# Sheet2.net
KiCad netlist of a schematic drawn in Altium Designer
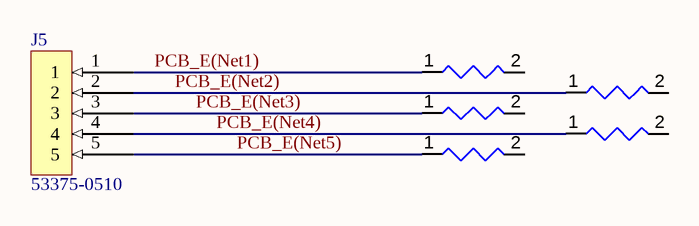
[diagram p0: Sheet2.SchDoc]

(export (version "E")
  (design (tool "Eeschema 10.0.6"))
  (components
    (comp (ref "J5")
      (value "53375-0510")
      (footprint "53375-0510-Footprint-1")
      (fields (field (name "MANUFACTURER") "Molex"))
      (libsource (lib "SCH") (part "CMP-002-00076-3"))
    )
    (comp (ref "R1")
      (value "Resistor 10k +/-1% 1206 250 mW")
      (footprint "RESC3216X60X45ML15T20")
      (description "Chip Resistor, 10 KOhm, +/- 1%, 0.25 W, -55 to 155 degC, 1206 (3216 Metric)")
      (fields (field (name "TOLERANCE") "1%") (field (name "POWER") "250mW"))
      (libsource (lib "SCH") (part "RES-2"))
    )
    (comp (ref "R2")
      (value "Resistor 10k +/-1% 1206 250 mW")
      (footprint "RESC3216X60X45ML15T20")
      (description "Chip Resistor, 10 KOhm, +/- 1%, 0.25 W, -55 to 155 degC, 1206 (3216 Metric)")
      (fields (field (name "TOLERANCE") "1%") (field (name "POWER") "250mW"))
      (libsource (lib "SCH") (part "RES-2"))
    )
    (comp (ref "R3")
      (value "Resistor 10k +/-1% 1206 250 mW")
      (footprint "RESC3216X60X45ML15T20")
      (description "Chip Resistor, 10 KOhm, +/- 1%, 0.25 W, -55 to 155 degC, 1206 (3216 Metric)")
      (fields (field (name "TOLERANCE") "1%") (field (name "POWER") "250mW"))
      (libsource (lib "SCH") (part "RES-2"))
    )
    (comp (ref "R4")
      (value "Resistor 10k +/-1% 1206 250 mW")
      (footprint "RESC3216X60X45ML15T20")
      (description "Chip Resistor, 10 KOhm, +/- 1%, 0.25 W, -55 to 155 degC, 1206 (3216 Metric)")
      (fields (field (name "TOLERANCE") "1%") (field (name "POWER") "250mW"))
      (libsource (lib "SCH") (part "RES-2"))
    )
    (comp (ref "R5")
      (value "Resistor 10k +/-1% 1206 250 mW")
      (footprint "RESC3216X60X45ML15T20")
      (description "Chip Resistor, 10 KOhm, +/- 1%, 0.25 W, -55 to 155 degC, 1206 (3216 Metric)")
      (fields (field (name "TOLERANCE") "1%") (field (name "POWER") "250mW"))
      (libsource (lib "SCH") (part "RES-2"))
    )
  )
  (nets
    (net (code "1") (name "/PCB_E(Net1)") (class "Default")
      (node (ref "J5") (pin "1") (pinfunction "1_1") (pintype "input"))
      (node (ref "R1") (pin "1") (pinfunction "1_1") (pintype "passive"))
    )
    (net (code "2") (name "/PCB_E(Net2)") (class "Default")
      (node (ref "J5") (pin "2") (pinfunction "2_2") (pintype "input"))
      (node (ref "R2") (pin "1") (pinfunction "1_1") (pintype "passive"))
    )
    (net (code "3") (name "/PCB_E(Net3)") (class "Default")
      (node (ref "J5") (pin "3") (pinfunction "3_3") (pintype "input"))
      (node (ref "R3") (pin "1") (pinfunction "1_1") (pintype "passive"))
    )
    (net (code "4") (name "/PCB_E(Net4)") (class "Default")
      (node (ref "J5") (pin "4") (pinfunction "4_4") (pintype "input"))
      (node (ref "R4") (pin "1") (pinfunction "1_1") (pintype "passive"))
    )
    (net (code "5") (name "/PCB_E(Net5)") (class "Default")
      (node (ref "J5") (pin "5") (pinfunction "5_5") (pintype "input"))
      (node (ref "R5") (pin "1") (pinfunction "1_1") (pintype "passive"))
    )
    (net (code "6") (name "unconnected-(R1-Pad2)") (class "Default")
      (node (ref "R1") (pin "2") (pinfunction "2_2") (pintype "passive"))
    )
    (net (code "7") (name "unconnected-(R2-Pad2)") (class "Default")
      (node (ref "R2") (pin "2") (pinfunction "2_2") (pintype "passive"))
    )
    (net (code "8") (name "unconnected-(R3-Pad2)") (class "Default")
      (node (ref "R3") (pin "2") (pinfunction "2_2") (pintype "passive"))
    )
    (net (code "9") (name "unconnected-(R4-Pad2)") (class "Default")
      (node (ref "R4") (pin "2") (pinfunction "2_2") (pintype "passive"))
    )
    (net (code "10") (name "unconnected-(R5-Pad2)") (class "Default")
      (node (ref "R5") (pin "2") (pinfunction "2_2") (pintype "passive"))
    )
  )
)
